# Power_FT232.net
KiCad netlist of a schematic drawn in Altium Designer
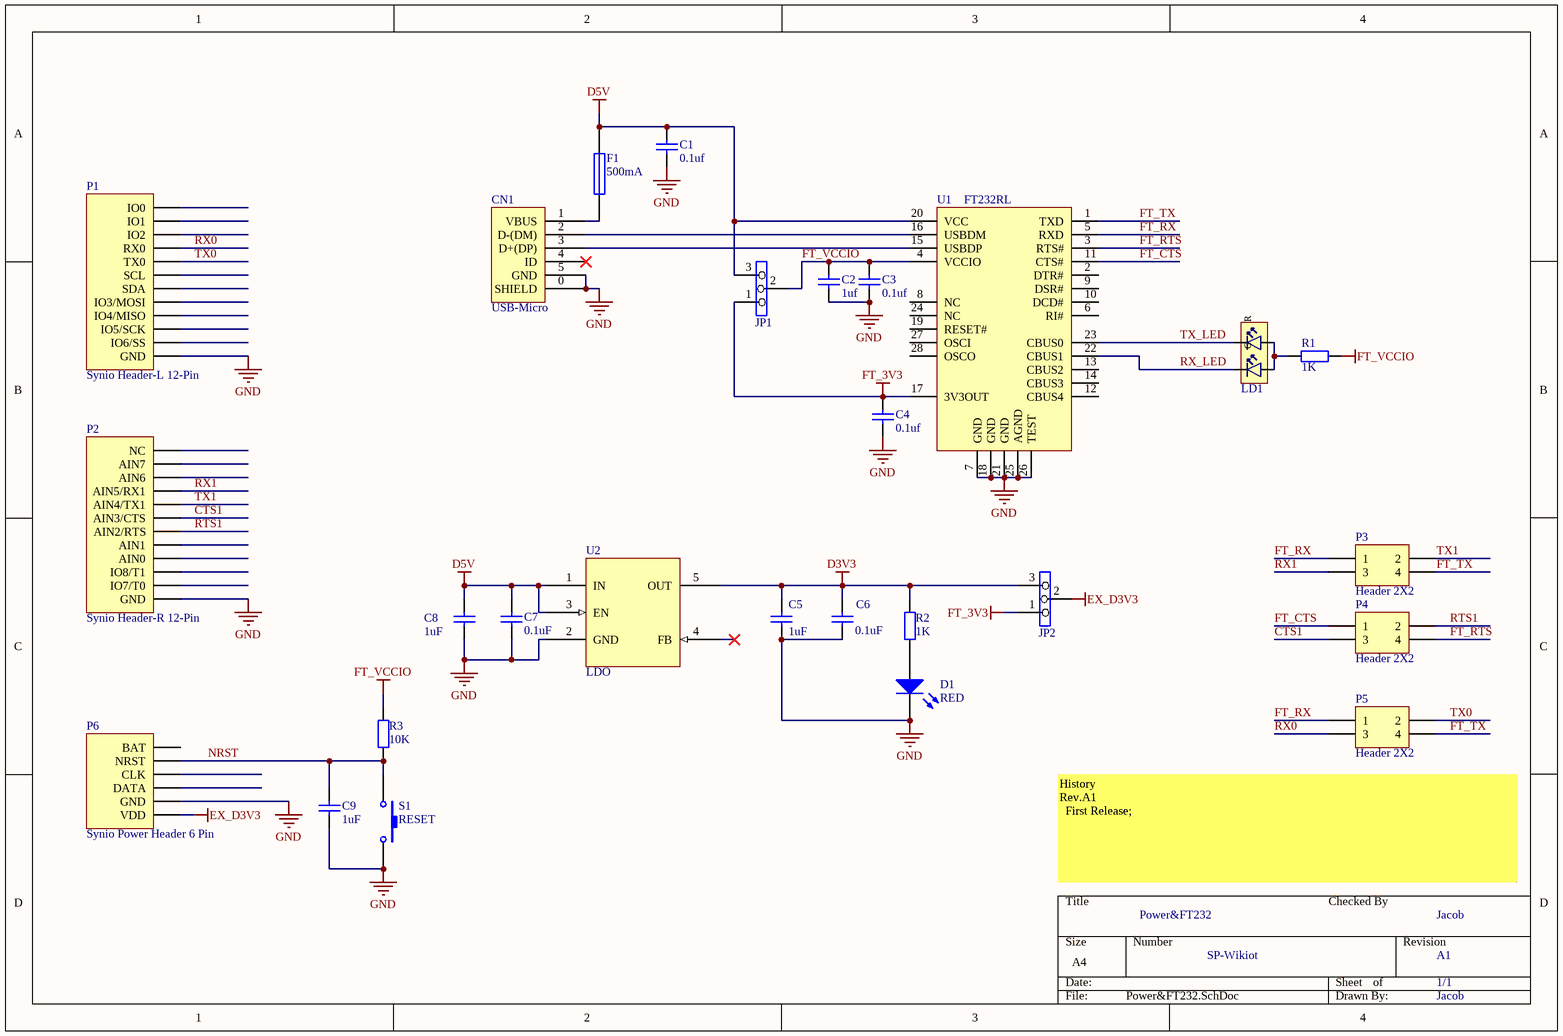
[diagram p0: Power&FT232.SchDoc]

(export (version "E")
  (design (tool "Eeschema 10.0.6"))
  (components
    (comp (ref "C1")
      (value "0.1uf")
      (footprint "C0603L")
      (description "Capacitor")
      (fields (field (name "Comment") "Cap") (field (name "PUBLISHER") "Altium Limited"))
      (libsource (lib "myintlib") (part "Cap"))
    )
    (comp (ref "C2")
      (value "1uf")
      (footprint "C0603L")
      (description "Capacitor")
      (fields (field (name "Comment") "Cap") (field (name "PUBLISHER") "Altium Limited"))
      (libsource (lib "myintlib") (part "Cap"))
    )
    (comp (ref "C3")
      (value "0.1uf")
      (footprint "C0603L")
      (description "Capacitor")
      (fields (field (name "Comment") "Cap") (field (name "PUBLISHER") "Altium Limited"))
      (libsource (lib "myintlib") (part "Cap"))
    )
    (comp (ref "C4")
      (value "0.1uf")
      (footprint "C0603L")
      (description "Capacitor")
      (fields (field (name "Comment") "Cap") (field (name "PUBLISHER") "Altium Limited"))
      (libsource (lib "myintlib") (part "Cap"))
    )
    (comp (ref "C5")
      (value "1uF")
      (footprint "C0603L")
      (description "Capacitor")
      (libsource (lib "Studio") (part "Cap"))
    )
    (comp (ref "C6")
      (value "0.1uF")
      (footprint "C0603L")
      (description "Capacitor")
      (libsource (lib "Studio") (part "Cap"))
    )
    (comp (ref "C7")
      (value "0.1uF")
      (footprint "C0603L")
      (description "Capacitor")
      (libsource (lib "Studio") (part "Cap"))
    )
    (comp (ref "C8")
      (value "1uF")
      (footprint "C0603L")
      (description "Capacitor")
      (libsource (lib "Studio") (part "Cap"))
    )
    (comp (ref "C9")
      (value "1uF")
      (footprint "C0603L")
      (description "Capacitor")
      (fields (field (name "PUBLISHER") "Altium Limited"))
      (libsource (lib "Miscellaneous Devices") (part "Cap"))
    )
    (comp (ref "CN1")
      (value "USB-Micro")
      (footprint "USB-MICRO-Female-Lite")
      (libsource (lib "Connector") (part "USB-Micro"))
    )
    (comp (ref "D1")
      (value "RED")
      (footprint "0603pn")
      (description "Typical INFRARED GaAs LED")
      (fields (field (name "PUBLISHER") "Altium Limited"))
      (libsource (lib "Miscellaneous Devices") (part "LED0"))
    )
    (comp (ref "F1")
      (value "500mA")
      (footprint "0805")
      (description "Fuse")
      (fields (field (name "PUBLISHER") "Altium Limited"))
      (libsource (lib "Studio") (part "Fuse 1"))
    )
    (comp (ref "JP1") (value "Jumper3") (footprint "HDR1X3/2.54MM") (libsource (lib "Misc") (part "Jumper3")))
    (comp (ref "JP2") (value "Jumper3") (footprint "HDR1X3/2.54MM") (libsource (lib "Misc") (part "Jumper3")))
    (comp (ref "LD1")
      (value "LTST-C195KGJRKT")
      (footprint "0805-LED-Bi")
      (description "Avago, HSMF-A203 Bi-Color LED")
      (fields
        (field (name "MANUFACTURER") "Lite-On Inc")
        (field (name "2ND SOURCE PART NUMBER") "859-LTST-C195KGJRKT")
        (field (name "PUBLISHER") "Nordic Semiconductor")
      )
      (libsource (lib "Misc") (part "LED-DUAL"))
    )
    (comp (ref "P1")
      (value "Synio Header-L 12-Pin")
      (footprint "HDR1X12-L/2.54MM")
      (description "Synio Header-L, 12-Pin")
      (fields (field (name "PUBLISHER") "Altium Limited"))
      (libsource (lib "Connector") (part "Synio Header-L 12-Pin"))
    )
    (comp (ref "P2")
      (value "Synio Header-R 12-Pin")
      (footprint "HDR1X12-L/2.54MM")
      (description "Synio Header-R, 12-Pin")
      (fields (field (name "PUBLISHER") "Altium Limited"))
      (libsource (lib "Connector") (part "Synio Header-R 12-Pin"))
    )
    (comp (ref "P3")
      (value "Header 2X2")
      (footprint "HDR2X2/2.54MM")
      (description "Header, 2-Pin, Dual row")
      (fields (field (name "PUBLISHER") "Altium Limited"))
      (libsource (lib "Miscellaneous Connectors") (part "Header 2X2"))
    )
    (comp (ref "P4")
      (value "Header 2X2")
      (footprint "HDR2X2/2.54MM")
      (description "Header, 2-Pin, Dual row")
      (fields (field (name "PUBLISHER") "Altium Limited"))
      (libsource (lib "Miscellaneous Connectors") (part "Header 2X2"))
    )
    (comp (ref "P5")
      (value "Header 2X2")
      (footprint "HDR2X2/2.54MM")
      (description "Header, 2-Pin, Dual row")
      (fields (field (name "PUBLISHER") "Altium Limited"))
      (libsource (lib "Miscellaneous Connectors") (part "Header 2X2"))
    )
    (comp (ref "P6")
      (value "Synio Power Header 6 Pin")
      (footprint "HDR1X6-L/2.54MM")
      (libsource (lib "Connector") (part "Synio Power Header 6 Pin"))
    )
    (comp (ref "R1")
      (value "1K")
      (footprint "0603M")
      (description "Resistor")
      (fields (field (name "PUBLISHER") "Altium Limited"))
      (libsource (lib "") (part "Res2_2"))
    )
    (comp (ref "R2")
      (value "1K")
      (footprint "0603M")
      (description "Resistor")
      (fields (field (name "PUBLISHER") "Altium Limited"))
      (libsource (lib "Miscellaneous Devices") (part "Res2"))
    )
    (comp (ref "R3")
      (value "10K")
      (footprint "0603M")
      (description "Resistor")
      (fields (field (name "PUBLISHER") "Altium Limited"))
      (libsource (lib "") (part "Res2_1"))
    )
    (comp (ref "S1")
      (value "RESET")
      (footprint "KEY-2x4-SMD")
      (description "Switch")
      (fields (field (name "PUBLISHER") "Altium Limited"))
      (libsource (lib "Miscellaneous Devices") (part "SW-PB"))
    )
    (comp (ref "U1")
      (value "FT232RL")
      (footprint "SSOP-28_M")
      (description "USB UART IC")
      (libsource (lib "myintlib") (part "FT232RL"))
    )
    (comp (ref "U2")
      (value "LDO")
      (footprint "SOT23-5")
      (description "General LDO SOT23-5")
      (libsource (lib "Power") (part "LDO-SOT23-5"))
    )
  )
  (nets
    (net (code "1") (name "/CTS1") (class "Default")
      (node (ref "P2") (pin "7") (pinfunction "AIN3/CTS_7") (pintype "passive"))
      (node (ref "P4") (pin "3") (pinfunction "3_3") (pintype "passive"))
    )
    (net (code "2") (name "/FT_CTS") (class "Default")
      (node (ref "P4") (pin "1") (pinfunction "1_1") (pintype "passive"))
      (node (ref "U1") (pin "11") (pinfunction "CTS#_11") (pintype "passive"))
    )
    (net (code "3") (name "/FT_RTS") (class "Default")
      (node (ref "P4") (pin "4") (pinfunction "4_4") (pintype "passive"))
      (node (ref "U1") (pin "3") (pinfunction "RTS#_3") (pintype "passive"))
    )
    (net (code "4") (name "/FT_RX") (class "Default")
      (node (ref "P3") (pin "1") (pinfunction "1_1") (pintype "passive"))
      (node (ref "P5") (pin "1") (pinfunction "1_1") (pintype "passive"))
      (node (ref "U1") (pin "5") (pinfunction "RXD_5") (pintype "passive"))
    )
    (net (code "5") (name "/FT_TX") (class "Default")
      (node (ref "P3") (pin "4") (pinfunction "4_4") (pintype "passive"))
      (node (ref "P5") (pin "4") (pinfunction "4_4") (pintype "passive"))
      (node (ref "U1") (pin "1") (pinfunction "TXD_1") (pintype "passive"))
    )
    (net (code "6") (name "/NRST") (class "Default")
      (node (ref "C9") (pin "2") (pinfunction "2_2") (pintype "passive"))
      (node (ref "P6") (pin "5") (pinfunction "NRST_5") (pintype "passive"))
      (node (ref "R3") (pin "2") (pinfunction "2_2") (pintype "passive"))
      (node (ref "S1") (pin "2") (pinfunction "2_2") (pintype "passive"))
    )
    (net (code "7") (name "/RTS1") (class "Default")
      (node (ref "P2") (pin "6") (pinfunction "AIN2/RTS_6") (pintype "passive"))
      (node (ref "P4") (pin "2") (pinfunction "2_2") (pintype "passive"))
    )
    (net (code "8") (name "/RX0") (class "Default")
      (node (ref "P1") (pin "9") (pinfunction "RX0_9") (pintype "passive"))
      (node (ref "P5") (pin "3") (pinfunction "3_3") (pintype "passive"))
    )
    (net (code "9") (name "/RX1") (class "Default")
      (node (ref "P2") (pin "9") (pinfunction "AIN5/RX1_9") (pintype "passive"))
      (node (ref "P3") (pin "3") (pinfunction "3_3") (pintype "passive"))
    )
    (net (code "10") (name "/RX_LED") (class "Default")
      (node (ref "LD1") (pin "1") (pinfunction "C1_1") (pintype "passive"))
      (node (ref "U1") (pin "22") (pinfunction "CBUS1_22") (pintype "passive"))
    )
    (net (code "11") (name "/TX0") (class "Default")
      (node (ref "P1") (pin "8") (pinfunction "TX0_8") (pintype "passive"))
      (node (ref "P5") (pin "2") (pinfunction "2_2") (pintype "passive"))
    )
    (net (code "12") (name "/TX1") (class "Default")
      (node (ref "P2") (pin "8") (pinfunction "AIN4/TX1_8") (pintype "passive"))
      (node (ref "P3") (pin "2") (pinfunction "2_2") (pintype "passive"))
    )
    (net (code "13") (name "/TX_LED") (class "Default")
      (node (ref "LD1") (pin "2") (pinfunction "C2_2") (pintype "passive"))
      (node (ref "U1") (pin "23") (pinfunction "CBUS0_23") (pintype "passive"))
    )
    (net (code "14") (name "D3V3") (class "Default")
      (node (ref "C5") (pin "2") (pinfunction "2_2") (pintype "passive"))
      (node (ref "C6") (pin "2") (pinfunction "2_2") (pintype "passive"))
      (node (ref "JP2") (pin "3") (pintype "passive"))
      (node (ref "R2") (pin "2") (pinfunction "2_2") (pintype "passive"))
      (node (ref "U2") (pin "5") (pinfunction "OUT_5") (pintype "power_in"))
    )
    (net (code "15") (name "D5V") (class "Default")
      (node (ref "C1") (pin "2") (pinfunction "2_2") (pintype "passive"))
      (node (ref "C7") (pin "2") (pinfunction "2_2") (pintype "passive"))
      (node (ref "C8") (pin "2") (pinfunction "2_2") (pintype "passive"))
      (node (ref "F1") (pin "1") (pinfunction "1_1") (pintype "passive"))
      (node (ref "JP1") (pin "3") (pintype "passive"))
      (node (ref "U1") (pin "20") (pinfunction "VCC_20") (pintype "passive"))
      (node (ref "U2") (pin "1") (pinfunction "IN_1") (pintype "power_in"))
      (node (ref "U2") (pin "3") (pinfunction "EN_3") (pintype "input"))
    )
    (net (code "16") (name "EX_D3V3") (class "Default")
      (node (ref "JP2") (pin "2") (pintype "passive"))
      (node (ref "P6") (pin "1") (pinfunction "VDD_1") (pintype "passive"))
    )
    (net (code "17") (name "FT_3V3") (class "Default")
      (node (ref "C4") (pin "2") (pinfunction "2_2") (pintype "passive"))
      (node (ref "JP1") (pin "1") (pintype "passive"))
      (node (ref "JP2") (pin "1") (pintype "passive"))
      (node (ref "U1") (pin "17") (pinfunction "3V3OUT_17") (pintype "passive"))
    )
    (net (code "18") (name "FT_VCCIO") (class "Default")
      (node (ref "C2") (pin "2") (pinfunction "2_2") (pintype "passive"))
      (node (ref "C3") (pin "2") (pinfunction "2_2") (pintype "passive"))
      (node (ref "JP1") (pin "2") (pintype "passive"))
      (node (ref "R1") (pin "1") (pinfunction "1_1") (pintype "passive"))
      (node (ref "R3") (pin "1") (pinfunction "1_1") (pintype "passive"))
      (node (ref "U1") (pin "4") (pinfunction "VCCIO_4") (pintype "passive"))
    )
    (net (code "19") (name "GND") (class "Default")
      (node (ref "C1") (pin "1") (pinfunction "1_1") (pintype "passive"))
      (node (ref "C2") (pin "1") (pinfunction "1_1") (pintype "passive"))
      (node (ref "C3") (pin "1") (pinfunction "1_1") (pintype "passive"))
      (node (ref "C4") (pin "1") (pinfunction "1_1") (pintype "passive"))
      (node (ref "C5") (pin "1") (pinfunction "1_1") (pintype "passive"))
      (node (ref "C6") (pin "1") (pinfunction "1_1") (pintype "passive"))
      (node (ref "C7") (pin "1") (pinfunction "1_1") (pintype "passive"))
      (node (ref "C8") (pin "1") (pinfunction "1_1") (pintype "passive"))
      (node (ref "C9") (pin "1") (pinfunction "1_1") (pintype "passive"))
      (node (ref "CN1") (pin "0") (pinfunction "SHIELD_0") (pintype "passive"))
      (node (ref "CN1") (pin "5") (pinfunction "GND_5") (pintype "passive"))
      (node (ref "D1") (pin "2") (pinfunction "K_2") (pintype "passive"))
      (node (ref "P1") (pin "1") (pinfunction "GND_1") (pintype "passive"))
      (node (ref "P2") (pin "1") (pinfunction "GND_1") (pintype "passive"))
      (node (ref "P6") (pin "2") (pinfunction "GND_2") (pintype "passive"))
      (node (ref "S1") (pin "1") (pinfunction "1_1") (pintype "passive"))
      (node (ref "U1") (pin "18") (pinfunction "GND_18") (pintype "passive"))
      (node (ref "U1") (pin "21") (pinfunction "GND_21") (pintype "passive"))
      (node (ref "U1") (pin "25") (pinfunction "AGND_25") (pintype "passive"))
      (node (ref "U1") (pin "26") (pinfunction "TEST_26") (pintype "passive"))
      (node (ref "U1") (pin "7") (pinfunction "GND_7") (pintype "passive"))
      (node (ref "U2") (pin "2") (pinfunction "GND_2") (pintype "power_in"))
    )
    (net (code "20") (name "Net-(CN1-D+(DP))") (class "Default")
      (node (ref "CN1") (pin "3") (pinfunction "D+(DP)_3") (pintype "passive"))
      (node (ref "U1") (pin "15") (pinfunction "USBDP_15") (pintype "passive"))
    )
    (net (code "21") (name "Net-(CN1-D-(DM))") (class "Default")
      (node (ref "CN1") (pin "2") (pinfunction "D-(DM)_2") (pintype "passive"))
      (node (ref "U1") (pin "16") (pinfunction "USBDM_16") (pintype "passive"))
    )
    (net (code "22") (name "Net-(CN1-VBUS)") (class "Default")
      (node (ref "CN1") (pin "1") (pinfunction "VBUS_1") (pintype "passive"))
      (node (ref "F1") (pin "2") (pinfunction "2_2") (pintype "passive"))
    )
    (net (code "23") (name "Net-(D1-A)") (class "Default")
      (node (ref "D1") (pin "1") (pinfunction "A_1") (pintype "passive"))
      (node (ref "R2") (pin "1") (pinfunction "1_1") (pintype "passive"))
    )
    (net (code "24") (name "Net-(LD1-A1)") (class "Default")
      (node (ref "LD1") (pin "3") (pinfunction "A2_3") (pintype "passive"))
      (node (ref "LD1") (pin "4") (pinfunction "A1_4") (pintype "passive"))
      (node (ref "R1") (pin "2") (pinfunction "2_2") (pintype "passive"))
    )
    (net (code "25") (name "unconnected-(CN1-ID-Pad4)") (class "Default")
      (node (ref "CN1") (pin "4") (pinfunction "ID_4") (pintype "passive+no_connect"))
    )
    (net (code "26") (name "unconnected-(P1-IO0-Pad12)") (class "Default")
      (node (ref "P1") (pin "12") (pinfunction "IO0_12") (pintype "passive"))
    )
    (net (code "27") (name "unconnected-(P1-IO1-Pad11)") (class "Default")
      (node (ref "P1") (pin "11") (pinfunction "IO1_11") (pintype "passive"))
    )
    (net (code "28") (name "unconnected-(P1-IO2-Pad10)") (class "Default")
      (node (ref "P1") (pin "10") (pinfunction "IO2_10") (pintype "passive"))
    )
    (net (code "29") (name "unconnected-(P1-IO3{slash}MOSI-Pad5)") (class "Default")
      (node (ref "P1") (pin "5") (pinfunction "IO3/MOSI_5") (pintype "passive"))
    )
    (net (code "30") (name "unconnected-(P1-IO4{slash}MISO-Pad4)") (class "Default")
      (node (ref "P1") (pin "4") (pinfunction "IO4/MISO_4") (pintype "passive"))
    )
    (net (code "31") (name "unconnected-(P1-IO5{slash}SCK-Pad3)") (class "Default")
      (node (ref "P1") (pin "3") (pinfunction "IO5/SCK_3") (pintype "passive"))
    )
    (net (code "32") (name "unconnected-(P1-IO6{slash}SS-Pad2)") (class "Default")
      (node (ref "P1") (pin "2") (pinfunction "IO6/SS_2") (pintype "passive"))
    )
    (net (code "33") (name "unconnected-(P1-SCL-Pad7)") (class "Default")
      (node (ref "P1") (pin "7") (pinfunction "SCL_7") (pintype "passive"))
    )
    (net (code "34") (name "unconnected-(P1-SDA-Pad6)") (class "Default")
      (node (ref "P1") (pin "6") (pinfunction "SDA_6") (pintype "passive"))
    )
    (net (code "35") (name "unconnected-(P2-AIN0-Pad4)") (class "Default")
      (node (ref "P2") (pin "4") (pinfunction "AIN0_4") (pintype "passive"))
    )
    (net (code "36") (name "unconnected-(P2-AIN1-Pad5)") (class "Default")
      (node (ref "P2") (pin "5") (pinfunction "AIN1_5") (pintype "passive"))
    )
    (net (code "37") (name "unconnected-(P2-AIN6-Pad10)") (class "Default")
      (node (ref "P2") (pin "10") (pinfunction "AIN6_10") (pintype "passive"))
    )
    (net (code "38") (name "unconnected-(P2-AIN7-Pad11)") (class "Default")
      (node (ref "P2") (pin "11") (pinfunction "AIN7_11") (pintype "passive"))
    )
    (net (code "39") (name "unconnected-(P2-IO7{slash}T0-Pad2)") (class "Default")
      (node (ref "P2") (pin "2") (pinfunction "IO7/T0_2") (pintype "passive"))
    )
    (net (code "40") (name "unconnected-(P2-IO8{slash}T1-Pad3)") (class "Default")
      (node (ref "P2") (pin "3") (pinfunction "IO8/T1_3") (pintype "passive"))
    )
    (net (code "41") (name "unconnected-(P2-NC-Pad12)") (class "Default")
      (node (ref "P2") (pin "12") (pinfunction "NC_12") (pintype "passive"))
    )
    (net (code "42") (name "unconnected-(P6-BAT-Pad6)") (class "Default")
      (node (ref "P6") (pin "6") (pinfunction "BAT_6") (pintype "passive"))
    )
    (net (code "43") (name "unconnected-(P6-CLK-Pad4)") (class "Default")
      (node (ref "P6") (pin "4") (pinfunction "CLK_4") (pintype "passive"))
    )
    (net (code "44") (name "unconnected-(P6-DATA-Pad3)") (class "Default")
      (node (ref "P6") (pin "3") (pinfunction "DATA_3") (pintype "passive"))
    )
    (net (code "45") (name "unconnected-(U1-CBUS2-Pad13)") (class "Default")
      (node (ref "U1") (pin "13") (pinfunction "CBUS2_13") (pintype "passive"))
    )
    (net (code "46") (name "unconnected-(U1-CBUS3-Pad14)") (class "Default")
      (node (ref "U1") (pin "14") (pinfunction "CBUS3_14") (pintype "passive"))
    )
    (net (code "47") (name "unconnected-(U1-CBUS4-Pad12)") (class "Default")
      (node (ref "U1") (pin "12") (pinfunction "CBUS4_12") (pintype "passive"))
    )
    (net (code "48") (name "unconnected-(U1-DCD#-Pad10)") (class "Default")
      (node (ref "U1") (pin "10") (pinfunction "DCD#_10") (pintype "passive"))
    )
    (net (code "49") (name "unconnected-(U1-DSR#-Pad9)") (class "Default")
      (node (ref "U1") (pin "9") (pinfunction "DSR#_9") (pintype "passive"))
    )
    (net (code "50") (name "unconnected-(U1-DTR#-Pad2)") (class "Default")
      (node (ref "U1") (pin "2") (pinfunction "DTR#_2") (pintype "passive"))
    )
    (net (code "51") (name "unconnected-(U1-NC-Pad8)") (class "Default")
      (node (ref "U1") (pin "8") (pinfunction "NC_8") (pintype "passive"))
    )
    (net (code "52") (name "unconnected-(U1-NC-Pad24)") (class "Default")
      (node (ref "U1") (pin "24") (pinfunction "NC_24") (pintype "passive"))
    )
    (net (code "53") (name "unconnected-(U1-OSCI-Pad27)") (class "Default")
      (node (ref "U1") (pin "27") (pinfunction "OSCI_27") (pintype "passive"))
    )
    (net (code "54") (name "unconnected-(U1-OSCO-Pad28)") (class "Default")
      (node (ref "U1") (pin "28") (pinfunction "OSCO_28") (pintype "passive"))
    )
    (net (code "55") (name "unconnected-(U1-RESET#-Pad19)") (class "Default")
      (node (ref "U1") (pin "19") (pinfunction "RESET#_19") (pintype "passive"))
    )
    (net (code "56") (name "unconnected-(U1-RI#-Pad6)") (class "Default")
      (node (ref "U1") (pin "6") (pinfunction "RI#_6") (pintype "passive"))
    )
    (net (code "57") (name "unconnected-(U2-FB-Pad4)") (class "Default")
      (node (ref "U2") (pin "4") (pinfunction "FB_4") (pintype "input+no_connect"))
    )
  )
)
